# driver.net
KiCad netlist of a schematic drawn in Altium Designer
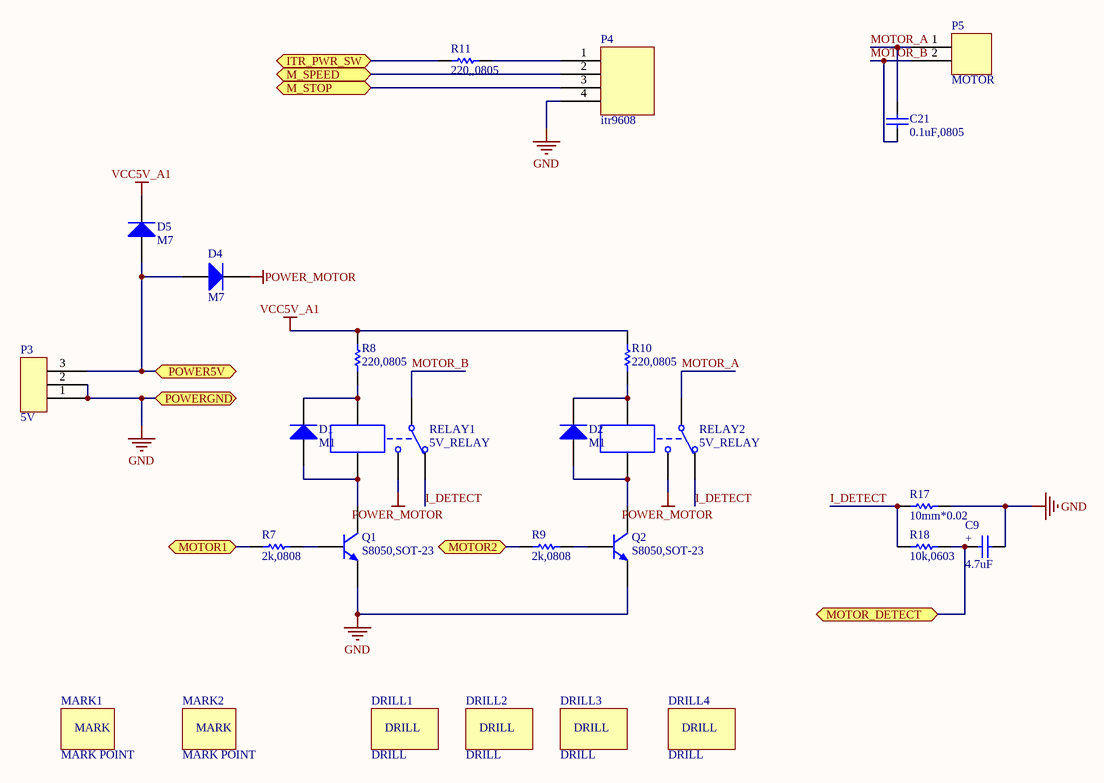
[diagram p0: driver.SchDoc]

(export (version "E")
  (design (tool "Eeschema 10.0.6"))
  (components
    (comp (ref "C9")
      (value "4.7uF")
      (footprint "CDIP2")
      (description "electric capacitor")
      (libsource (lib "Inte") (part "E_CAP"))
    )
    (comp (ref "C21")
      (value "0.1uF,0805")
      (footprint "C0805")
      (description "Capacitor")
      (fields (field (name "PUBLISHER") "Altium Limited"))
      (libsource (lib "Inte") (part "CAP"))
    )
    (comp (ref "D1")
      (value "M1")
      (footprint "DO214AC")
      (description "diode")
      (libsource (lib "Inte") (part "DIODE"))
    )
    (comp (ref "D2")
      (value "M1")
      (footprint "DO214AC")
      (description "diode")
      (libsource (lib "Inte") (part "DIODE"))
    )
    (comp (ref "D4")
      (value "M7")
      (footprint "DO214AC")
      (description "diode")
      (libsource (lib "Inte") (part "DIODE"))
    )
    (comp (ref "D5")
      (value "M7")
      (footprint "DO214AC")
      (description "diode")
      (libsource (lib "Inte") (part "DIODE"))
    )
    (comp (ref "DRILL1") (value "DRILL") (footprint "DRILL_3MM") (libsource (lib "Inte") (part "DRILL")))
    (comp (ref "DRILL2") (value "DRILL") (footprint "DRILL_3MM") (libsource (lib "Inte") (part "DRILL")))
    (comp (ref "DRILL3") (value "DRILL") (footprint "DRILL_3MM") (libsource (lib "Inte") (part "DRILL")))
    (comp (ref "DRILL4") (value "DRILL") (footprint "DRILL_3MM") (libsource (lib "Inte") (part "DRILL")))
    (comp (ref "MARK1")
      (value "MARK POINT")
      (footprint "MARK_POINT")
      (libsource (lib "Inte") (part "MARK_POINT"))
    )
    (comp (ref "MARK2")
      (value "MARK POINT")
      (footprint "MARK_POINT")
      (libsource (lib "Inte") (part "MARK_POINT"))
    )
    (comp (ref "P3")
      (value "5V")
      (footprint "HDR3X1")
      (description "Header 3X1,3-Pin")
      (libsource (lib "Inte") (part "Header 3X1"))
    )
    (comp (ref "P4")
      (value "itr9608")
      (footprint "HDR4X1")
      (description "ITR9608")
      (libsource (lib "Inte") (part "Header 4X1"))
    )
    (comp (ref "P5") (value "MOTOR") (footprint "HDR2X1") (libsource (lib "Inte") (part "Header 2X1")))
    (comp (ref "Q1")
      (value "S8050,SOT-23")
      (footprint "SOT23")
      (description "transistor")
      (libsource (lib "Inte") (part "NPN"))
    )
    (comp (ref "Q2") (value "S8050,SOT-23") (footprint "SOT23") (libsource (lib "Inte") (part "NPN")))
    (comp (ref "R7")
      (value "2k,0808")
      (footprint "R0805")
      (description "Resistor")
      (fields (field (name "PUBLISHER") "Altium Limited"))
      (libsource (lib "Inte") (part "Res1"))
    )
    (comp (ref "R8")
      (value "220,0805")
      (footprint "R0805")
      (description "Resistor")
      (fields (field (name "PUBLISHER") "Altium Limited"))
      (libsource (lib "Inte") (part "Res1"))
    )
    (comp (ref "R9")
      (value "2k,0808")
      (footprint "R0805")
      (description "Resistor")
      (fields (field (name "PUBLISHER") "Altium Limited"))
      (libsource (lib "Inte") (part "Res1"))
    )
    (comp (ref "R10")
      (value "220,0805")
      (footprint "R0805")
      (description "Resistor")
      (fields (field (name "PUBLISHER") "Altium Limited"))
      (libsource (lib "Inte") (part "Res1"))
    )
    (comp (ref "R11")
      (value "220,,0805")
      (footprint "R0805")
      (description "Resistor")
      (fields (field (name "PUBLISHER") "Altium Limited"))
      (libsource (lib "Inte") (part "Res1"))
    )
    (comp (ref "R17") (value "10mm*0.02") (footprint "Ri") (libsource (lib "Inte") (part "Ri")))
    (comp (ref "R18")
      (value "10k,0603")
      (footprint "R0805")
      (description "Resistor")
      (fields (field (name "PUBLISHER") "Altium Limited"))
      (libsource (lib "Inte") (part "Res1"))
    )
    (comp (ref "RELAY1")
      (value "5V_RELAY")
      (footprint "RELAY_5V_5PIN")
      (description "relay")
      (libsource (lib "Inte") (part "RELAY"))
    )
    (comp (ref "RELAY2")
      (value "5V_RELAY")
      (footprint "RELAY_5V_5PIN")
      (description "relay")
      (libsource (lib "Inte") (part "RELAY"))
    )
  )
  (nets
    (net (code "1") (name "/ITR_PWR_SW") (class "Default")
      (node (ref "R11") (pin "2") (pinfunction "2_2") (pintype "passive"))
    )
    (net (code "2") (name "/I_DETECT") (class "Default")
      (node (ref "R17") (pin "1") (pinfunction "1_1") (pintype "passive"))
      (node (ref "R18") (pin "1") (pinfunction "1_1") (pintype "passive"))
      (node (ref "RELAY1") (pin "2") (pinfunction "2_2") (pintype "passive"))
      (node (ref "RELAY2") (pin "2") (pinfunction "2_2") (pintype "passive"))
    )
    (net (code "3") (name "/MOTOR1") (class "Default")
      (node (ref "R7") (pin "2") (pinfunction "2_2") (pintype "passive"))
    )
    (net (code "4") (name "/MOTOR2") (class "Default")
      (node (ref "R9") (pin "1") (pinfunction "1_1") (pintype "passive"))
    )
    (net (code "5") (name "/MOTOR_A") (class "Default")
      (node (ref "C21") (pin "1") (pinfunction "1_1") (pintype "passive"))
      (node (ref "P5") (pin "1") (pinfunction "1_1") (pintype "passive"))
      (node (ref "RELAY2") (pin "1") (pinfunction "1_1") (pintype "passive"))
    )
    (net (code "6") (name "/MOTOR_B") (class "Default")
      (node (ref "C21") (pin "2") (pinfunction "2_2") (pintype "passive"))
      (node (ref "P5") (pin "2") (pinfunction "2_2") (pintype "passive"))
      (node (ref "RELAY1") (pin "1") (pinfunction "1_1") (pintype "passive"))
    )
    (net (code "7") (name "/MOTOR_DETECT") (class "Default")
      (node (ref "C9") (pin "1") (pinfunction "1_1") (pintype "passive"))
      (node (ref "R18") (pin "2") (pinfunction "2_2") (pintype "passive"))
    )
    (net (code "8") (name "/M_SPEED") (class "Default")
      (node (ref "P4") (pin "2") (pinfunction "2_2") (pintype "passive"))
    )
    (net (code "9") (name "/M_STOP") (class "Default")
      (node (ref "P4") (pin "3") (pinfunction "3_3") (pintype "passive"))
    )
    (net (code "10") (name "/POWER5V") (class "Default")
      (node (ref "D4") (pin "1") (pinfunction "A_1") (pintype "passive"))
      (node (ref "D5") (pin "1") (pinfunction "A_1") (pintype "passive"))
      (node (ref "P3") (pin "3") (pinfunction "3_3") (pintype "passive"))
    )
    (net (code "11") (name "GND") (class "Default")
      (node (ref "C9") (pin "2") (pinfunction "2_2") (pintype "passive"))
      (node (ref "P3") (pin "1") (pinfunction "1_1") (pintype "passive"))
      (node (ref "P3") (pin "2") (pinfunction "2_2") (pintype "passive"))
      (node (ref "P4") (pin "4") (pinfunction "4_4") (pintype "passive"))
      (node (ref "Q1") (pin "3") (pinfunction "E_3") (pintype "passive"))
      (node (ref "Q2") (pin "3") (pinfunction "E_3") (pintype "passive"))
      (node (ref "R17") (pin "2") (pinfunction "2_2") (pintype "passive"))
    )
    (net (code "12") (name "Net-(D1-A)") (class "Default")
      (node (ref "D1") (pin "1") (pinfunction "A_1") (pintype "passive"))
      (node (ref "Q1") (pin "1") (pinfunction "C_1") (pintype "passive"))
      (node (ref "RELAY1") (pin "5") (pinfunction "5_5") (pintype "passive"))
    )
    (net (code "13") (name "Net-(D1-K)") (class "Default")
      (node (ref "D1") (pin "2") (pinfunction "K_2") (pintype "passive"))
      (node (ref "R8") (pin "1") (pinfunction "1_1") (pintype "passive"))
      (node (ref "RELAY1") (pin "4") (pinfunction "4_4") (pintype "passive"))
    )
    (net (code "14") (name "Net-(D2-A)") (class "Default")
      (node (ref "D2") (pin "1") (pinfunction "A_1") (pintype "passive"))
      (node (ref "Q2") (pin "1") (pinfunction "C_1") (pintype "passive"))
      (node (ref "RELAY2") (pin "5") (pinfunction "5_5") (pintype "passive"))
    )
    (net (code "15") (name "Net-(D2-K)") (class "Default")
      (node (ref "D2") (pin "2") (pinfunction "K_2") (pintype "passive"))
      (node (ref "R10") (pin "1") (pinfunction "1_1") (pintype "passive"))
      (node (ref "RELAY2") (pin "4") (pinfunction "4_4") (pintype "passive"))
    )
    (net (code "16") (name "Net-(P4-Pad1)") (class "Default")
      (node (ref "P4") (pin "1") (pinfunction "1_1") (pintype "passive"))
      (node (ref "R11") (pin "1") (pinfunction "1_1") (pintype "passive"))
    )
    (net (code "17") (name "Net-(Q1-B)") (class "Default")
      (node (ref "Q1") (pin "2") (pinfunction "B_2") (pintype "passive"))
      (node (ref "R7") (pin "1") (pinfunction "1_1") (pintype "passive"))
    )
    (net (code "18") (name "Net-(Q2-B)") (class "Default")
      (node (ref "Q2") (pin "2") (pinfunction "B_2") (pintype "passive"))
      (node (ref "R9") (pin "2") (pinfunction "2_2") (pintype "passive"))
    )
    (net (code "19") (name "POWER_MOTOR") (class "Default")
      (node (ref "D4") (pin "2") (pinfunction "K_2") (pintype "passive"))
      (node (ref "RELAY1") (pin "3") (pinfunction "3_3") (pintype "passive"))
      (node (ref "RELAY2") (pin "3") (pinfunction "3_3") (pintype "passive"))
    )
    (net (code "20") (name "VCC5V_A1") (class "Default")
      (node (ref "D5") (pin "2") (pinfunction "K_2") (pintype "passive"))
      (node (ref "R10") (pin "2") (pinfunction "2_2") (pintype "passive"))
      (node (ref "R8") (pin "2") (pinfunction "2_2") (pintype "passive"))
    )
  )
)
